# weathermon_v1.net
KiCad netlist of a schematic drawn in EasyEDA
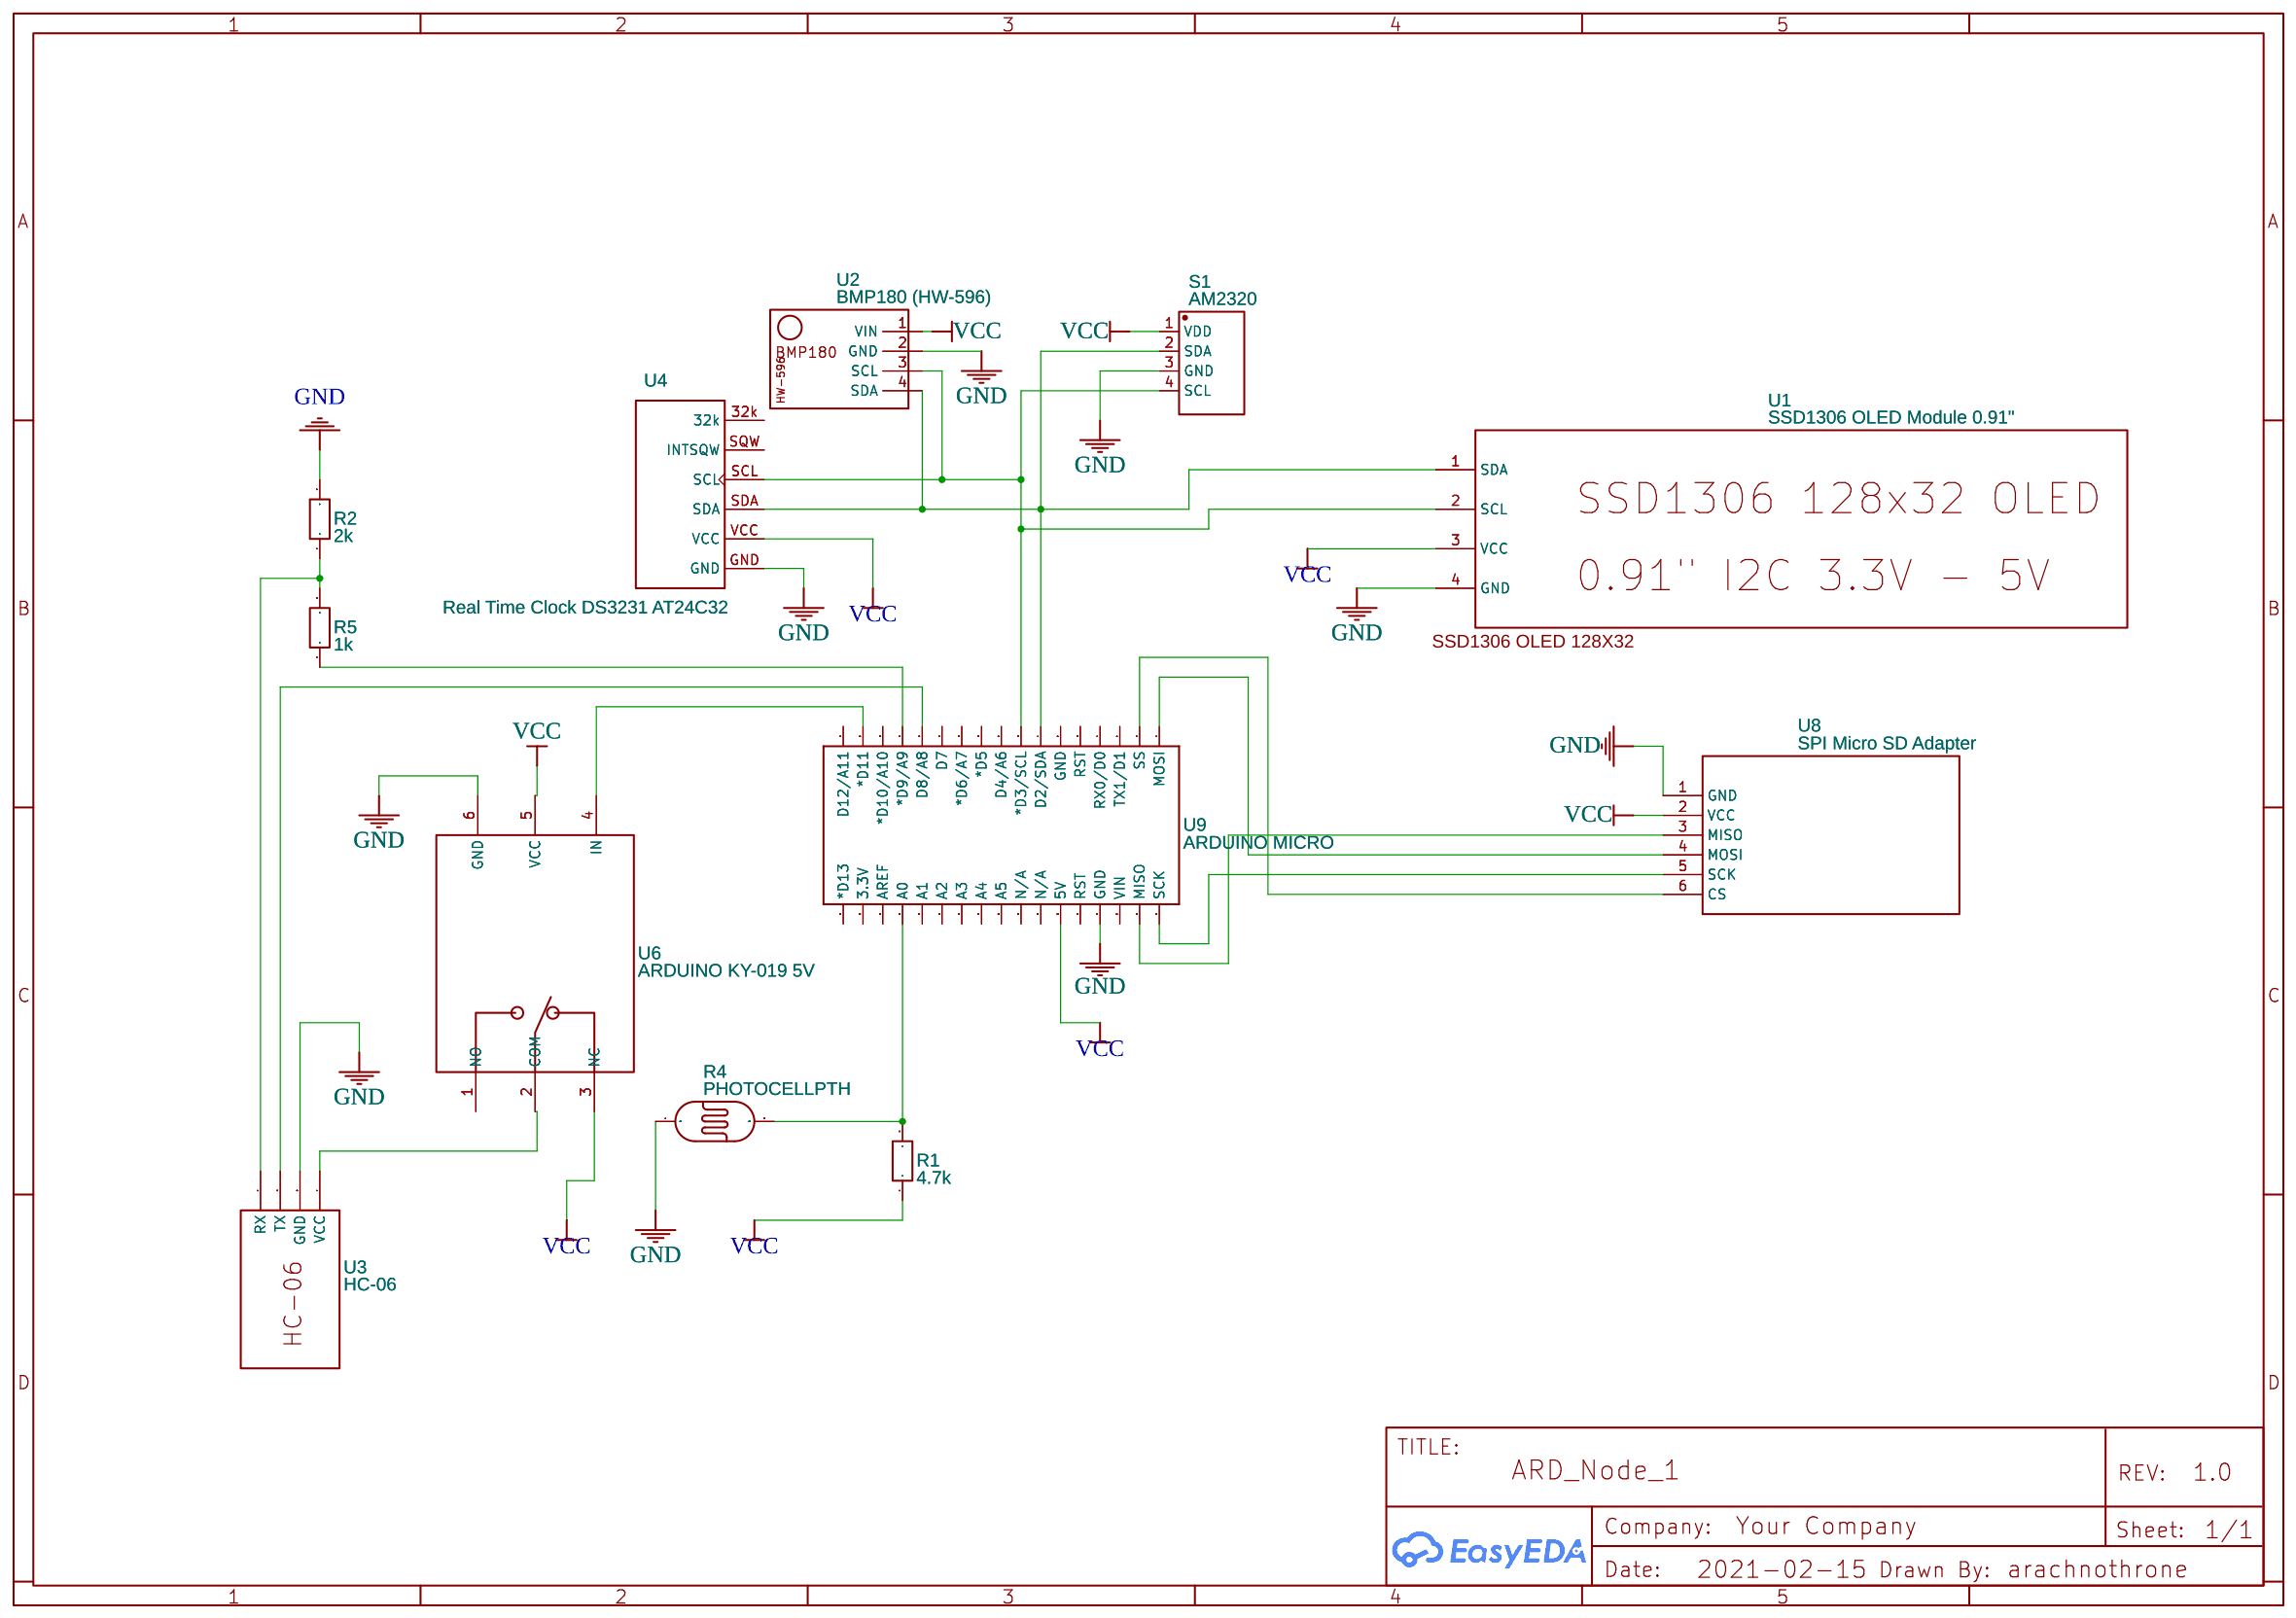
[diagram p0: schematic sheet]

(export (version "E")
  (design (tool "Eeschema 10.0.6"))
  (components
    (comp (ref "R1") (value "4.7k") (libsource (lib "") (part "R_0603_EU")))
    (comp (ref "R2") (value "2k") (libsource (lib "") (part "R_0603_EU")))
    (comp (ref "R4") (value "PHOTOCELLPTH") (libsource (lib "") (part "PHOTOCELLPTH")))
    (comp (ref "R5") (value "1k") (libsource (lib "") (part "R_0603_EU")))
    (comp (ref "S1")
      (value "AM2320")
      (fields (field (name "BOM_Supplier Part") "C87932"))
      (libsource (lib "") (part "AM2320"))
    )
    (comp (ref "U1")
      (value "SSD1306 OLED Module 0.91\"")
      (fields (field (name "BOM_Manufacturer Part") "SSD1306 0.91"))
      (libsource (lib "") (part "SSD1306 OLED Module 0.91{dblquote}"))
    )
    (comp (ref "U2") (value "BMP180 (HW-596)") (libsource (lib "") (part "BMP180 (HW-596)")))
    (comp (ref "U3") (value "HC-06") (libsource (lib "") (part "HC-06")))
    (comp (ref "U4")
      (value "Real Time Clock DS3231 AT24C32")
      (libsource (lib "") (part "Real Time Clock DS3231 AT24C32"))
    )
    (comp (ref "U6")
      (value "ARDUINO KY-019 5V")
      (fields
        (field (name "BOM_Manufacturer Part") "SRD-05VDC-SL-C")
        (field (name "BOM_Supplier Part") "undefined")
      )
      (libsource (lib "") (part "ARDUINO KY-019 5V"))
    )
    (comp (ref "U8") (value "SPI Micro SD Adapter") (libsource (lib "") (part "SPI Micro SD Adapter")))
    (comp (ref "U9") (value "ARDUINO MICRO") (libsource (lib "") (part "ARDUINO MICRO")))
  )
  (nets
    (net (code "1") (name "GND") (class "Default")
      (node (ref "R2") (pin "2") (pinfunction "2_2") (pintype "unspecified"))
      (node (ref "R4") (pin "1") (pinfunction "P$1_1") (pintype "unspecified"))
      (node (ref "S1") (pin "3") (pinfunction "GND_3") (pintype "unspecified"))
      (node (ref "U1") (pin "4") (pinfunction "GND_4") (pintype "unspecified"))
      (node (ref "U2") (pin "2") (pinfunction "GND_2") (pintype "unspecified"))
      (node (ref "U3") (pin "3") (pinfunction "GND_3") (pintype "unspecified"))
      (node (ref "U4") (pin "GND") (pinfunction "GND_GND") (pintype "passive"))
      (node (ref "U6") (pin "6") (pinfunction "GND_6") (pintype "unspecified"))
      (node (ref "U8") (pin "1") (pinfunction "GND_1") (pintype "unspecified"))
      (node (ref "U9") (pin "31") (pinfunction "GND_31") (pintype "unspecified"))
    )
    (net (code "2") (name "Net-(R4-P$2)") (class "Default")
      (node (ref "R1") (pin "2") (pinfunction "2_2") (pintype "unspecified"))
      (node (ref "R4") (pin "2") (pinfunction "P$2_2") (pintype "unspecified"))
      (node (ref "U9") (pin "21") (pinfunction "A0_21") (pintype "unspecified"))
    )
    (net (code "3") (name "Net-(S1-SCL)") (class "Default")
      (node (ref "S1") (pin "4") (pinfunction "SCL_4") (pintype "unspecified"))
      (node (ref "U1") (pin "2") (pinfunction "SCL_2") (pintype "unspecified"))
      (node (ref "U2") (pin "3") (pinfunction "SCL_3") (pintype "unspecified"))
      (node (ref "U4") (pin "SCL") (pinfunction "SCL_SCL") (pintype "bidirectional"))
      (node (ref "U9") (pin "8") (pinfunction "*D3/SCL_8") (pintype "unspecified"))
    )
    (net (code "4") (name "Net-(S1-SDA)") (class "Default")
      (node (ref "S1") (pin "2") (pinfunction "SDA_2") (pintype "unspecified"))
      (node (ref "U1") (pin "1") (pinfunction "SDA_1") (pintype "unspecified"))
      (node (ref "U2") (pin "4") (pinfunction "SDA_4") (pintype "unspecified"))
      (node (ref "U4") (pin "SDA") (pinfunction "SDA_SDA") (pintype "bidirectional"))
      (node (ref "U9") (pin "7") (pinfunction "D2/SDA_7") (pintype "unspecified"))
    )
    (net (code "5") (name "Net-(U3-RX)") (class "Default")
      (node (ref "R2") (pin "1") (pinfunction "1_1") (pintype "unspecified"))
      (node (ref "R5") (pin "2") (pinfunction "2_2") (pintype "unspecified"))
      (node (ref "U3") (pin "1") (pinfunction "RX_1") (pintype "unspecified"))
    )
    (net (code "6") (name "Net-(U3-TX)") (class "Default")
      (node (ref "U3") (pin "2") (pinfunction "TX_2") (pintype "unspecified"))
      (node (ref "U9") (pin "13") (pinfunction "D8/A8_13") (pintype "unspecified"))
    )
    (net (code "7") (name "Net-(U3-VCC)") (class "Default")
      (node (ref "U3") (pin "4") (pinfunction "VCC_4") (pintype "unspecified"))
      (node (ref "U6") (pin "2") (pinfunction "COM_2") (pintype "unspecified"))
    )
    (net (code "8") (name "Net-(U6-IN)") (class "Default")
      (node (ref "U6") (pin "4") (pinfunction "IN_4") (pintype "unspecified"))
      (node (ref "U9") (pin "16") (pinfunction "*D11_16") (pintype "unspecified"))
    )
    (net (code "9") (name "Net-(U8-CS)") (class "Default")
      (node (ref "U8") (pin "6") (pinfunction "CS_6") (pintype "unspecified"))
      (node (ref "U9") (pin "2") (pinfunction "SS_2") (pintype "unspecified"))
    )
    (net (code "10") (name "Net-(U8-MISO)") (class "Default")
      (node (ref "U8") (pin "3") (pinfunction "MISO_3") (pintype "unspecified"))
      (node (ref "U9") (pin "33") (pinfunction "MISO_33") (pintype "unspecified"))
    )
    (net (code "11") (name "Net-(U8-MOSI)") (class "Default")
      (node (ref "U8") (pin "4") (pinfunction "MOSI_4") (pintype "unspecified"))
      (node (ref "U9") (pin "1") (pinfunction "MOSI_1") (pintype "unspecified"))
    )
    (net (code "12") (name "Net-(U8-SCK)") (class "Default")
      (node (ref "U8") (pin "5") (pinfunction "SCK_5") (pintype "unspecified"))
      (node (ref "U9") (pin "34") (pinfunction "SCK_34") (pintype "unspecified"))
    )
    (net (code "13") (name "Net-(U9-*D9{slash}A9)") (class "Default")
      (node (ref "R5") (pin "1") (pinfunction "1_1") (pintype "unspecified"))
      (node (ref "U9") (pin "14") (pinfunction "*D9/A9_14") (pintype "unspecified"))
    )
    (net (code "14") (name "VCC") (class "Default")
      (node (ref "R1") (pin "1") (pinfunction "1_1") (pintype "unspecified"))
      (node (ref "S1") (pin "1") (pinfunction "VDD_1") (pintype "unspecified"))
      (node (ref "U1") (pin "3") (pinfunction "VCC_3") (pintype "unspecified"))
      (node (ref "U2") (pin "1") (pinfunction "VIN_1") (pintype "unspecified"))
      (node (ref "U4") (pin "VCC") (pinfunction "VCC_VCC") (pintype "passive"))
      (node (ref "U6") (pin "3") (pinfunction "NC_3") (pintype "unspecified"))
      (node (ref "U6") (pin "5") (pinfunction "VCC_5") (pintype "unspecified"))
      (node (ref "U8") (pin "2") (pinfunction "VCC_2") (pintype "unspecified"))
      (node (ref "U9") (pin "29") (pinfunction "5V_29") (pintype "unspecified"))
    )
    (net (code "15") (name "unconnected-(U4-INTSQW-PadSQW)") (class "Default")
      (node (ref "U4") (pin "SQW") (pinfunction "INTSQW_SQW") (pintype "unspecified"))
    )
    (net (code "16") (name "unconnected-(U4-Pad32k)") (class "Default")
      (node (ref "U4") (pin "32k") (pinfunction "32k_32k") (pintype "unspecified"))
    )
    (net (code "17") (name "unconnected-(U6-NO-Pad1)") (class "Default")
      (node (ref "U6") (pin "1") (pinfunction "NO_1") (pintype "unspecified"))
    )
    (net (code "18") (name "unconnected-(U9-*D5-Pad10)") (class "Default")
      (node (ref "U9") (pin "10") (pinfunction "*D5_10") (pintype "unspecified"))
    )
    (net (code "19") (name "unconnected-(U9-*D6{slash}A7-Pad11)") (class "Default")
      (node (ref "U9") (pin "11") (pinfunction "*D6/A7_11") (pintype "unspecified"))
    )
    (net (code "20") (name "unconnected-(U9-*D10{slash}A10-Pad15)") (class "Default")
      (node (ref "U9") (pin "15") (pinfunction "*D10/A10_15") (pintype "unspecified"))
    )
    (net (code "21") (name "unconnected-(U9-*D13-Pad18)") (class "Default")
      (node (ref "U9") (pin "18") (pinfunction "*D13_18") (pintype "unspecified"))
    )
    (net (code "22") (name "unconnected-(U9-3.3V-Pad19)") (class "Default")
      (node (ref "U9") (pin "19") (pinfunction "3.3V_19") (pintype "unspecified"))
    )
    (net (code "23") (name "unconnected-(U9-A1-Pad22)") (class "Default")
      (node (ref "U9") (pin "22") (pinfunction "A1_22") (pintype "unspecified"))
    )
    (net (code "24") (name "unconnected-(U9-A2-Pad23)") (class "Default")
      (node (ref "U9") (pin "23") (pinfunction "A2_23") (pintype "unspecified"))
    )
    (net (code "25") (name "unconnected-(U9-A3-Pad24)") (class "Default")
      (node (ref "U9") (pin "24") (pinfunction "A3_24") (pintype "unspecified"))
    )
    (net (code "26") (name "unconnected-(U9-A4-Pad25)") (class "Default")
      (node (ref "U9") (pin "25") (pinfunction "A4_25") (pintype "unspecified"))
    )
    (net (code "27") (name "unconnected-(U9-A5-Pad26)") (class "Default")
      (node (ref "U9") (pin "26") (pinfunction "A5_26") (pintype "unspecified"))
    )
    (net (code "28") (name "unconnected-(U9-AREF-Pad20)") (class "Default")
      (node (ref "U9") (pin "20") (pinfunction "AREF_20") (pintype "unspecified"))
    )
    (net (code "29") (name "unconnected-(U9-D4{slash}A6-Pad9)") (class "Default")
      (node (ref "U9") (pin "9") (pinfunction "D4/A6_9") (pintype "unspecified"))
    )
    (net (code "30") (name "unconnected-(U9-D7-Pad12)") (class "Default")
      (node (ref "U9") (pin "12") (pinfunction "D7_12") (pintype "unspecified"))
    )
    (net (code "31") (name "unconnected-(U9-D12{slash}A11-Pad17)") (class "Default")
      (node (ref "U9") (pin "17") (pinfunction "D12/A11_17") (pintype "unspecified"))
    )
    (net (code "32") (name "unconnected-(U9-GND-Pad6)") (class "Default")
      (node (ref "U9") (pin "6") (pinfunction "GND_6") (pintype "unspecified"))
    )
    (net (code "33") (name "unconnected-(U9-N{slash}A-Pad27)") (class "Default")
      (node (ref "U9") (pin "27") (pinfunction "N/A_27") (pintype "unspecified"))
    )
    (net (code "34") (name "unconnected-(U9-N{slash}A-Pad28)") (class "Default")
      (node (ref "U9") (pin "28") (pinfunction "N/A_28") (pintype "unspecified"))
    )
    (net (code "35") (name "unconnected-(U9-RST-Pad5)") (class "Default")
      (node (ref "U9") (pin "5") (pinfunction "RST_5") (pintype "unspecified"))
    )
    (net (code "36") (name "unconnected-(U9-RST-Pad30)") (class "Default")
      (node (ref "U9") (pin "30") (pinfunction "RST_30") (pintype "unspecified"))
    )
    (net (code "37") (name "unconnected-(U9-RX0{slash}D0-Pad4)") (class "Default")
      (node (ref "U9") (pin "4") (pinfunction "RX0/D0_4") (pintype "unspecified"))
    )
    (net (code "38") (name "unconnected-(U9-TX1{slash}D1-Pad3)") (class "Default")
      (node (ref "U9") (pin "3") (pinfunction "TX1/D1_3") (pintype "unspecified"))
    )
    (net (code "39") (name "unconnected-(U9-VIN-Pad32)") (class "Default")
      (node (ref "U9") (pin "32") (pinfunction "VIN_32") (pintype "unspecified"))
    )
  )
)
